# sch.net
KiCad netlist of a schematic drawn in Altium Designer
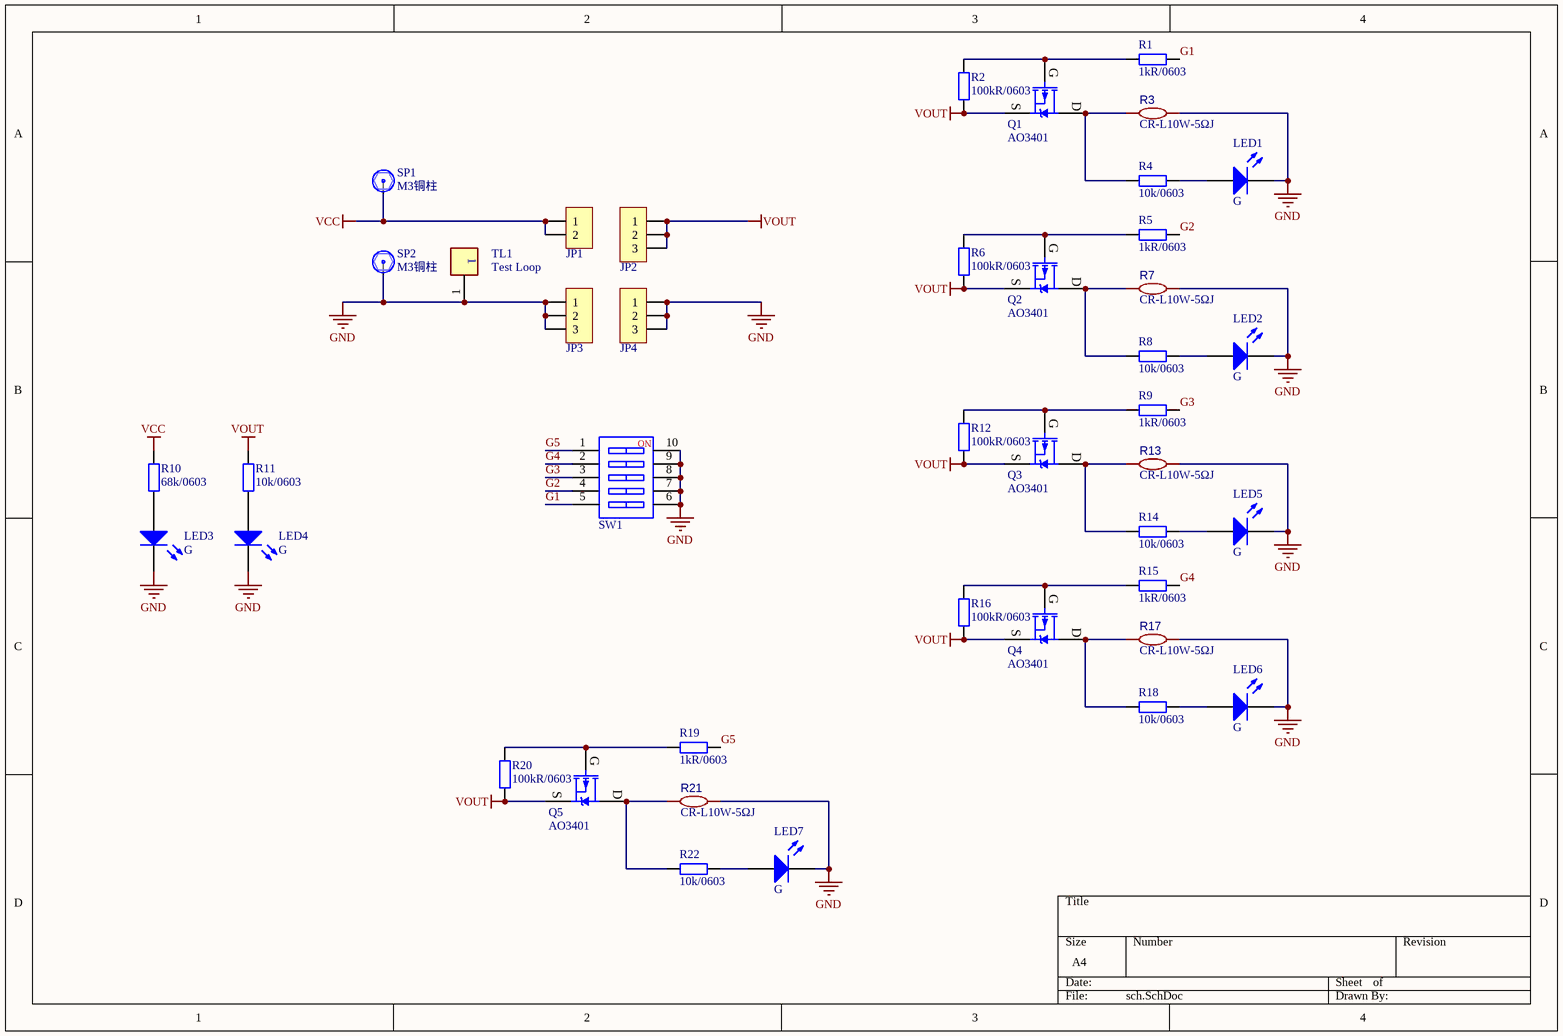
[diagram p0: sch.SchDoc]

(export (version "E")
  (design (tool "Eeschema 10.0.6"))
  (components
    (comp (ref "JP1")
      (value "HDR-1X2")
      (footprint "HDR2.54-M-LI-2P")
      (description "2P接插件")
      (libsource (lib "5.5 - 2.54mm连接器(KF2EDGK_XH2.54_2.54排针排母)") (part "Header 2"))
    )
    (comp (ref "JP2")
      (value "HDR-1X3")
      (footprint "HDR2.54-M-LI-3P")
      (description "3P接插件")
      (libsource (lib "5.5 - 2.54mm连接器(KF2EDGK_XH2.54_2.54排针排母)") (part "Header 3"))
    )
    (comp (ref "JP3")
      (value "HDR-1X3")
      (footprint "HDR2.54-M-LI-3P")
      (description "3P接插件")
      (libsource (lib "") (part "Header 3_1"))
    )
    (comp (ref "JP4")
      (value "HDR-1X3")
      (footprint "HDR2.54-M-LI-3P")
      (description "3P接插件")
      (libsource (lib "5.5 - 2.54mm连接器(KF2EDGK_XH2.54_2.54排针排母)") (part "Header 3"))
    )
    (comp (ref "LED1")
      (value "G")
      (footprint "LED0603_B")
      (description "贴片LED")
      (libsource (lib "0.3 - LED发光二极管-IR二极管_接收管-光耦") (part "LED"))
    )
    (comp (ref "LED2")
      (value "G")
      (footprint "LED0603_B")
      (description "贴片LED")
      (libsource (lib "0.3 - LED发光二极管-IR二极管_接收管-光耦") (part "LED"))
    )
    (comp (ref "LED3")
      (value "G")
      (footprint "LED0603_B")
      (description "贴片LED")
      (libsource (lib "0.3 - LED发光二极管-IR二极管_接收管-光耦") (part "LED"))
    )
    (comp (ref "LED4")
      (value "G")
      (footprint "LED0603_B")
      (description "贴片LED")
      (libsource (lib "0.3 - LED发光二极管-IR二极管_接收管-光耦") (part "LED"))
    )
    (comp (ref "LED5")
      (value "G")
      (footprint "LED0603_B")
      (description "贴片LED")
      (libsource (lib "0.3 - LED发光二极管-IR二极管_接收管-光耦") (part "LED"))
    )
    (comp (ref "LED6")
      (value "G")
      (footprint "LED0603_B")
      (description "贴片LED")
      (libsource (lib "0.3 - LED发光二极管-IR二极管_接收管-光耦") (part "LED"))
    )
    (comp (ref "LED7")
      (value "G")
      (footprint "LED0603_B")
      (description "贴片LED")
      (libsource (lib "0.3 - LED发光二极管-IR二极管_接收管-光耦") (part "LED"))
    )
    (comp (ref "Q1")
      (value "AO3401")
      (footprint "SOT23-3N")
      (description "P沟道 30V/4.2A")
      (libsource (lib "0.4 - 三极管-场效应管-可控硅") (part "AO3401"))
    )
    (comp (ref "Q2")
      (value "AO3401")
      (footprint "SOT23-3N")
      (description "P沟道 30V/4.2A")
      (libsource (lib "0.4 - 三极管-场效应管-可控硅") (part "AO3401"))
    )
    (comp (ref "Q3")
      (value "AO3401")
      (footprint "SOT23-3N")
      (description "P沟道 30V/4.2A")
      (libsource (lib "0.4 - 三极管-场效应管-可控硅") (part "AO3401"))
    )
    (comp (ref "Q4")
      (value "AO3401")
      (footprint "SOT23-3N")
      (description "P沟道 30V/4.2A")
      (libsource (lib "0.4 - 三极管-场效应管-可控硅") (part "AO3401"))
    )
    (comp (ref "Q5")
      (value "AO3401")
      (footprint "SOT23-3N")
      (description "P沟道 30V/4.2A")
      (libsource (lib "0.4 - 三极管-场效应管-可控硅") (part "AO3401"))
    )
    (comp (ref "R1")
      (value "1kR/0603")
      (footprint "R0603_M")
      (description "贴片电阻")
      (libsource (lib "0.1 - 电阻-电容-电感-保险丝-晶振-晶体-磁珠-电位器-法拉电容-馈通电容") (part "R"))
    )
    (comp (ref "R2")
      (value "100kR/0603")
      (footprint "R0603_M")
      (description "贴片电阻")
      (libsource (lib "0.1 - 电阻-电容-电感-保险丝-晶振-晶体-磁珠-电位器-法拉电容-馈通电容") (part "R"))
    )
    (comp (ref "R3")
      (value "CR-L10W-5ΩJ")
      (footprint "RES-TH_BD9.5-L48.0-P52.00-D0.7")
      (libsource (lib "CR-L10W-10ΩJCR-L10W-10ΩJ") (part "CR-L10W-10ΩJ"))
    )
    (comp (ref "R4")
      (value "10k/0603")
      (footprint "R0603_M")
      (description "贴片电阻")
      (libsource (lib "0.1 - 电阻-电容-电感-保险丝-晶振-晶体-磁珠-电位器-法拉电容-馈通电容") (part "R"))
    )
    (comp (ref "R5")
      (value "1kR/0603")
      (footprint "R0603_M")
      (description "贴片电阻")
      (libsource (lib "0.1 - 电阻-电容-电感-保险丝-晶振-晶体-磁珠-电位器-法拉电容-馈通电容") (part "R"))
    )
    (comp (ref "R6")
      (value "100kR/0603")
      (footprint "R0603_M")
      (description "贴片电阻")
      (libsource (lib "0.1 - 电阻-电容-电感-保险丝-晶振-晶体-磁珠-电位器-法拉电容-馈通电容") (part "R"))
    )
    (comp (ref "R7")
      (value "CR-L10W-5ΩJ")
      (footprint "RES-TH_BD9.5-L48.0-P52.00-D0.7")
      (libsource (lib "CR-L10W-10ΩJCR-L10W-10ΩJ") (part "CR-L10W-10ΩJ"))
    )
    (comp (ref "R8")
      (value "10k/0603")
      (footprint "R0603_M")
      (description "贴片电阻")
      (libsource (lib "0.1 - 电阻-电容-电感-保险丝-晶振-晶体-磁珠-电位器-法拉电容-馈通电容") (part "R"))
    )
    (comp (ref "R9")
      (value "1kR/0603")
      (footprint "R0603_M")
      (description "贴片电阻")
      (libsource (lib "0.1 - 电阻-电容-电感-保险丝-晶振-晶体-磁珠-电位器-法拉电容-馈通电容") (part "R"))
    )
    (comp (ref "R10")
      (value "68k/0603")
      (footprint "R0603_M")
      (description "贴片电阻")
      (libsource (lib "0.1 - 电阻-电容-电感-保险丝-晶振-晶体-磁珠-电位器-法拉电容-馈通电容") (part "R"))
    )
    (comp (ref "R11")
      (value "10k/0603")
      (footprint "R0603_M")
      (description "贴片电阻")
      (libsource (lib "0.1 - 电阻-电容-电感-保险丝-晶振-晶体-磁珠-电位器-法拉电容-馈通电容") (part "R"))
    )
    (comp (ref "R12")
      (value "100kR/0603")
      (footprint "R0603_M")
      (description "贴片电阻")
      (libsource (lib "0.1 - 电阻-电容-电感-保险丝-晶振-晶体-磁珠-电位器-法拉电容-馈通电容") (part "R"))
    )
    (comp (ref "R13")
      (value "CR-L10W-5ΩJ")
      (footprint "RES-TH_BD9.5-L48.0-P52.00-D0.7")
      (libsource (lib "CR-L10W-10ΩJCR-L10W-10ΩJ") (part "CR-L10W-10ΩJ"))
    )
    (comp (ref "R14")
      (value "10k/0603")
      (footprint "R0603_M")
      (description "贴片电阻")
      (libsource (lib "0.1 - 电阻-电容-电感-保险丝-晶振-晶体-磁珠-电位器-法拉电容-馈通电容") (part "R"))
    )
    (comp (ref "R15")
      (value "1kR/0603")
      (footprint "R0603_M")
      (description "贴片电阻")
      (libsource (lib "0.1 - 电阻-电容-电感-保险丝-晶振-晶体-磁珠-电位器-法拉电容-馈通电容") (part "R"))
    )
    (comp (ref "R16")
      (value "100kR/0603")
      (footprint "R0603_M")
      (description "贴片电阻")
      (libsource (lib "0.1 - 电阻-电容-电感-保险丝-晶振-晶体-磁珠-电位器-法拉电容-馈通电容") (part "R"))
    )
    (comp (ref "R17")
      (value "CR-L10W-5ΩJ")
      (footprint "RES-TH_BD9.5-L48.0-P52.00-D0.7")
      (libsource (lib "CR-L10W-10ΩJCR-L10W-10ΩJ") (part "CR-L10W-10ΩJ"))
    )
    (comp (ref "R18")
      (value "10k/0603")
      (footprint "R0603_M")
      (description "贴片电阻")
      (libsource (lib "0.1 - 电阻-电容-电感-保险丝-晶振-晶体-磁珠-电位器-法拉电容-馈通电容") (part "R"))
    )
    (comp (ref "R19")
      (value "1kR/0603")
      (footprint "R0603_M")
      (description "贴片电阻")
      (libsource (lib "0.1 - 电阻-电容-电感-保险丝-晶振-晶体-磁珠-电位器-法拉电容-馈通电容") (part "R"))
    )
    (comp (ref "R20")
      (value "100kR/0603")
      (footprint "R0603_M")
      (description "贴片电阻")
      (libsource (lib "0.1 - 电阻-电容-电感-保险丝-晶振-晶体-磁珠-电位器-法拉电容-馈通电容") (part "R"))
    )
    (comp (ref "R21")
      (value "CR-L10W-5ΩJ")
      (footprint "RES-TH_BD9.5-L48.0-P52.00-D0.7")
      (libsource (lib "CR-L10W-10ΩJCR-L10W-10ΩJ") (part "CR-L10W-10ΩJ"))
    )
    (comp (ref "R22")
      (value "10k/0603")
      (footprint "R0603_M")
      (description "贴片电阻")
      (libsource (lib "0.1 - 电阻-电容-电感-保险丝-晶振-晶体-磁珠-电位器-法拉电容-馈通电容") (part "R"))
    )
    (comp (ref "SP1")
      (value "M3铜柱")
      (footprint "M3x4_N")
      (description "铜柱")
      (libsource (lib "0.5 - 按键_开关_蜂鸣器_电池_测试点_Mark点_铜柱") (part "铜柱大焊盘"))
    )
    (comp (ref "SP2")
      (value "M3铜柱")
      (footprint "M3x4_N")
      (description "铜柱")
      (libsource (lib "0.5 - 按键_开关_蜂鸣器_电池_测试点_Mark点_铜柱") (part "铜柱大焊盘"))
    )
    (comp (ref "SW1")
      (value "DIP-SW-5P")
      (footprint "SW DIP-5P")
      (description "5路拨码开关")
      (libsource (lib "0.5 - 按键_开关_蜂鸣器_电池_测试点_Mark点_铜柱") (part "DIP-SW-5P"))
    )
    (comp (ref "TL1")
      (value "Test Loop")
      (footprint "FP-5002-MFG")
      (description "PC TEST POINT MINIATURE WHITE")
      (libsource (lib "Altium Content Vault") (part "1e4615820a309e3ce90f9e6d957b7fa"))
    )
  )
  (nets
    (net (code "1") (name "/G1") (class "Default")
      (node (ref "R1") (pin "1") (pinfunction "1_1") (pintype "passive"))
      (node (ref "SW1") (pin "5") (pinfunction "5_5") (pintype "passive"))
    )
    (net (code "2") (name "/G2") (class "Default")
      (node (ref "R5") (pin "1") (pinfunction "1_1") (pintype "passive"))
      (node (ref "SW1") (pin "4") (pinfunction "4_4") (pintype "passive"))
    )
    (net (code "3") (name "/G3") (class "Default")
      (node (ref "R9") (pin "1") (pinfunction "1_1") (pintype "passive"))
      (node (ref "SW1") (pin "3") (pinfunction "3_3") (pintype "passive"))
    )
    (net (code "4") (name "/G4") (class "Default")
      (node (ref "R15") (pin "1") (pinfunction "1_1") (pintype "passive"))
      (node (ref "SW1") (pin "2") (pinfunction "2_2") (pintype "passive"))
    )
    (net (code "5") (name "/G5") (class "Default")
      (node (ref "R19") (pin "1") (pinfunction "1_1") (pintype "passive"))
      (node (ref "SW1") (pin "1") (pinfunction "1_1") (pintype "passive"))
    )
    (net (code "6") (name "GND") (class "Default")
      (node (ref "JP3") (pin "1") (pinfunction "1_1") (pintype "passive"))
      (node (ref "JP3") (pin "2") (pinfunction "2_2") (pintype "passive"))
      (node (ref "JP3") (pin "3") (pinfunction "3_3") (pintype "passive"))
      (node (ref "JP4") (pin "1") (pinfunction "1_1") (pintype "passive"))
      (node (ref "JP4") (pin "2") (pinfunction "2_2") (pintype "passive"))
      (node (ref "JP4") (pin "3") (pinfunction "3_3") (pintype "passive"))
      (node (ref "LED1") (pin "2") (pinfunction "K_2") (pintype "passive"))
      (node (ref "LED2") (pin "2") (pinfunction "K_2") (pintype "passive"))
      (node (ref "LED3") (pin "2") (pinfunction "K_2") (pintype "passive"))
      (node (ref "LED4") (pin "2") (pinfunction "K_2") (pintype "passive"))
      (node (ref "LED5") (pin "2") (pinfunction "K_2") (pintype "passive"))
      (node (ref "LED6") (pin "2") (pinfunction "K_2") (pintype "passive"))
      (node (ref "LED7") (pin "2") (pinfunction "K_2") (pintype "passive"))
      (node (ref "R13") (pin "2") (pinfunction "2_2") (pintype "passive"))
      (node (ref "R17") (pin "2") (pinfunction "2_2") (pintype "passive"))
      (node (ref "R21") (pin "2") (pinfunction "2_2") (pintype "passive"))
      (node (ref "R3") (pin "2") (pinfunction "2_2") (pintype "passive"))
      (node (ref "R7") (pin "2") (pinfunction "2_2") (pintype "passive"))
      (node (ref "SP2") (pin "1") (pinfunction "1_1") (pintype "passive"))
      (node (ref "SW1") (pin "10") (pinfunction "10_10") (pintype "passive"))
      (node (ref "SW1") (pin "6") (pinfunction "6_6") (pintype "passive"))
      (node (ref "SW1") (pin "7") (pinfunction "7_7") (pintype "passive"))
      (node (ref "SW1") (pin "8") (pinfunction "8_8") (pintype "passive"))
      (node (ref "SW1") (pin "9") (pinfunction "9_9") (pintype "passive"))
      (node (ref "TL1") (pin "1") (pinfunction "1_1") (pintype "passive"))
    )
    (net (code "7") (name "Net-(LED1-A)") (class "Default")
      (node (ref "LED1") (pin "1") (pinfunction "A_1") (pintype "passive"))
      (node (ref "R4") (pin "2") (pinfunction "2_2") (pintype "passive"))
    )
    (net (code "8") (name "Net-(LED2-A)") (class "Default")
      (node (ref "LED2") (pin "1") (pinfunction "A_1") (pintype "passive"))
      (node (ref "R8") (pin "2") (pinfunction "2_2") (pintype "passive"))
    )
    (net (code "9") (name "Net-(LED3-A)") (class "Default")
      (node (ref "LED3") (pin "1") (pinfunction "A_1") (pintype "passive"))
      (node (ref "R10") (pin "2") (pinfunction "2_2") (pintype "passive"))
    )
    (net (code "10") (name "Net-(LED4-A)") (class "Default")
      (node (ref "LED4") (pin "1") (pinfunction "A_1") (pintype "passive"))
      (node (ref "R11") (pin "2") (pinfunction "2_2") (pintype "passive"))
    )
    (net (code "11") (name "Net-(LED5-A)") (class "Default")
      (node (ref "LED5") (pin "1") (pinfunction "A_1") (pintype "passive"))
      (node (ref "R14") (pin "2") (pinfunction "2_2") (pintype "passive"))
    )
    (net (code "12") (name "Net-(LED6-A)") (class "Default")
      (node (ref "LED6") (pin "1") (pinfunction "A_1") (pintype "passive"))
      (node (ref "R18") (pin "2") (pinfunction "2_2") (pintype "passive"))
    )
    (net (code "13") (name "Net-(LED7-A)") (class "Default")
      (node (ref "LED7") (pin "1") (pinfunction "A_1") (pintype "passive"))
      (node (ref "R22") (pin "2") (pinfunction "2_2") (pintype "passive"))
    )
    (net (code "14") (name "Net-(Q1-D)") (class "Default")
      (node (ref "Q1") (pin "3") (pinfunction "D_3") (pintype "passive"))
      (node (ref "R3") (pin "1") (pinfunction "1_1") (pintype "passive"))
      (node (ref "R4") (pin "1") (pinfunction "1_1") (pintype "passive"))
    )
    (net (code "15") (name "Net-(Q1-G)") (class "Default")
      (node (ref "Q1") (pin "1") (pinfunction "G_1") (pintype "passive"))
      (node (ref "R1") (pin "2") (pinfunction "2_2") (pintype "passive"))
      (node (ref "R2") (pin "2") (pinfunction "2_2") (pintype "passive"))
    )
    (net (code "16") (name "Net-(Q2-D)") (class "Default")
      (node (ref "Q2") (pin "3") (pinfunction "D_3") (pintype "passive"))
      (node (ref "R7") (pin "1") (pinfunction "1_1") (pintype "passive"))
      (node (ref "R8") (pin "1") (pinfunction "1_1") (pintype "passive"))
    )
    (net (code "17") (name "Net-(Q2-G)") (class "Default")
      (node (ref "Q2") (pin "1") (pinfunction "G_1") (pintype "passive"))
      (node (ref "R5") (pin "2") (pinfunction "2_2") (pintype "passive"))
      (node (ref "R6") (pin "2") (pinfunction "2_2") (pintype "passive"))
    )
    (net (code "18") (name "Net-(Q3-D)") (class "Default")
      (node (ref "Q3") (pin "3") (pinfunction "D_3") (pintype "passive"))
      (node (ref "R13") (pin "1") (pinfunction "1_1") (pintype "passive"))
      (node (ref "R14") (pin "1") (pinfunction "1_1") (pintype "passive"))
    )
    (net (code "19") (name "Net-(Q3-G)") (class "Default")
      (node (ref "Q3") (pin "1") (pinfunction "G_1") (pintype "passive"))
      (node (ref "R12") (pin "2") (pinfunction "2_2") (pintype "passive"))
      (node (ref "R9") (pin "2") (pinfunction "2_2") (pintype "passive"))
    )
    (net (code "20") (name "Net-(Q4-D)") (class "Default")
      (node (ref "Q4") (pin "3") (pinfunction "D_3") (pintype "passive"))
      (node (ref "R17") (pin "1") (pinfunction "1_1") (pintype "passive"))
      (node (ref "R18") (pin "1") (pinfunction "1_1") (pintype "passive"))
    )
    (net (code "21") (name "Net-(Q4-G)") (class "Default")
      (node (ref "Q4") (pin "1") (pinfunction "G_1") (pintype "passive"))
      (node (ref "R15") (pin "2") (pinfunction "2_2") (pintype "passive"))
      (node (ref "R16") (pin "2") (pinfunction "2_2") (pintype "passive"))
    )
    (net (code "22") (name "Net-(Q5-D)") (class "Default")
      (node (ref "Q5") (pin "3") (pinfunction "D_3") (pintype "passive"))
      (node (ref "R21") (pin "1") (pinfunction "1_1") (pintype "passive"))
      (node (ref "R22") (pin "1") (pinfunction "1_1") (pintype "passive"))
    )
    (net (code "23") (name "Net-(Q5-G)") (class "Default")
      (node (ref "Q5") (pin "1") (pinfunction "G_1") (pintype "passive"))
      (node (ref "R19") (pin "2") (pinfunction "2_2") (pintype "passive"))
      (node (ref "R20") (pin "2") (pinfunction "2_2") (pintype "passive"))
    )
    (net (code "24") (name "VCC") (class "Default")
      (node (ref "JP1") (pin "1") (pinfunction "1_1") (pintype "passive"))
      (node (ref "JP1") (pin "2") (pinfunction "2_2") (pintype "passive"))
      (node (ref "R10") (pin "1") (pinfunction "1_1") (pintype "passive"))
      (node (ref "SP1") (pin "1") (pinfunction "1_1") (pintype "passive"))
    )
    (net (code "25") (name "VOUT") (class "Default")
      (node (ref "JP2") (pin "1") (pinfunction "1_1") (pintype "passive"))
      (node (ref "JP2") (pin "2") (pinfunction "2_2") (pintype "passive"))
      (node (ref "JP2") (pin "3") (pinfunction "3_3") (pintype "passive"))
      (node (ref "Q1") (pin "2") (pinfunction "S_2") (pintype "passive"))
      (node (ref "Q2") (pin "2") (pinfunction "S_2") (pintype "passive"))
      (node (ref "Q3") (pin "2") (pinfunction "S_2") (pintype "passive"))
      (node (ref "Q4") (pin "2") (pinfunction "S_2") (pintype "passive"))
      (node (ref "Q5") (pin "2") (pinfunction "S_2") (pintype "passive"))
      (node (ref "R11") (pin "1") (pinfunction "1_1") (pintype "passive"))
      (node (ref "R12") (pin "1") (pinfunction "1_1") (pintype "passive"))
      (node (ref "R16") (pin "1") (pinfunction "1_1") (pintype "passive"))
      (node (ref "R2") (pin "1") (pinfunction "1_1") (pintype "passive"))
      (node (ref "R20") (pin "1") (pinfunction "1_1") (pintype "passive"))
      (node (ref "R6") (pin "1") (pinfunction "1_1") (pintype "passive"))
    )
  )
)
